# Sheet1.net
KiCad netlist of a schematic drawn in Altium Designer
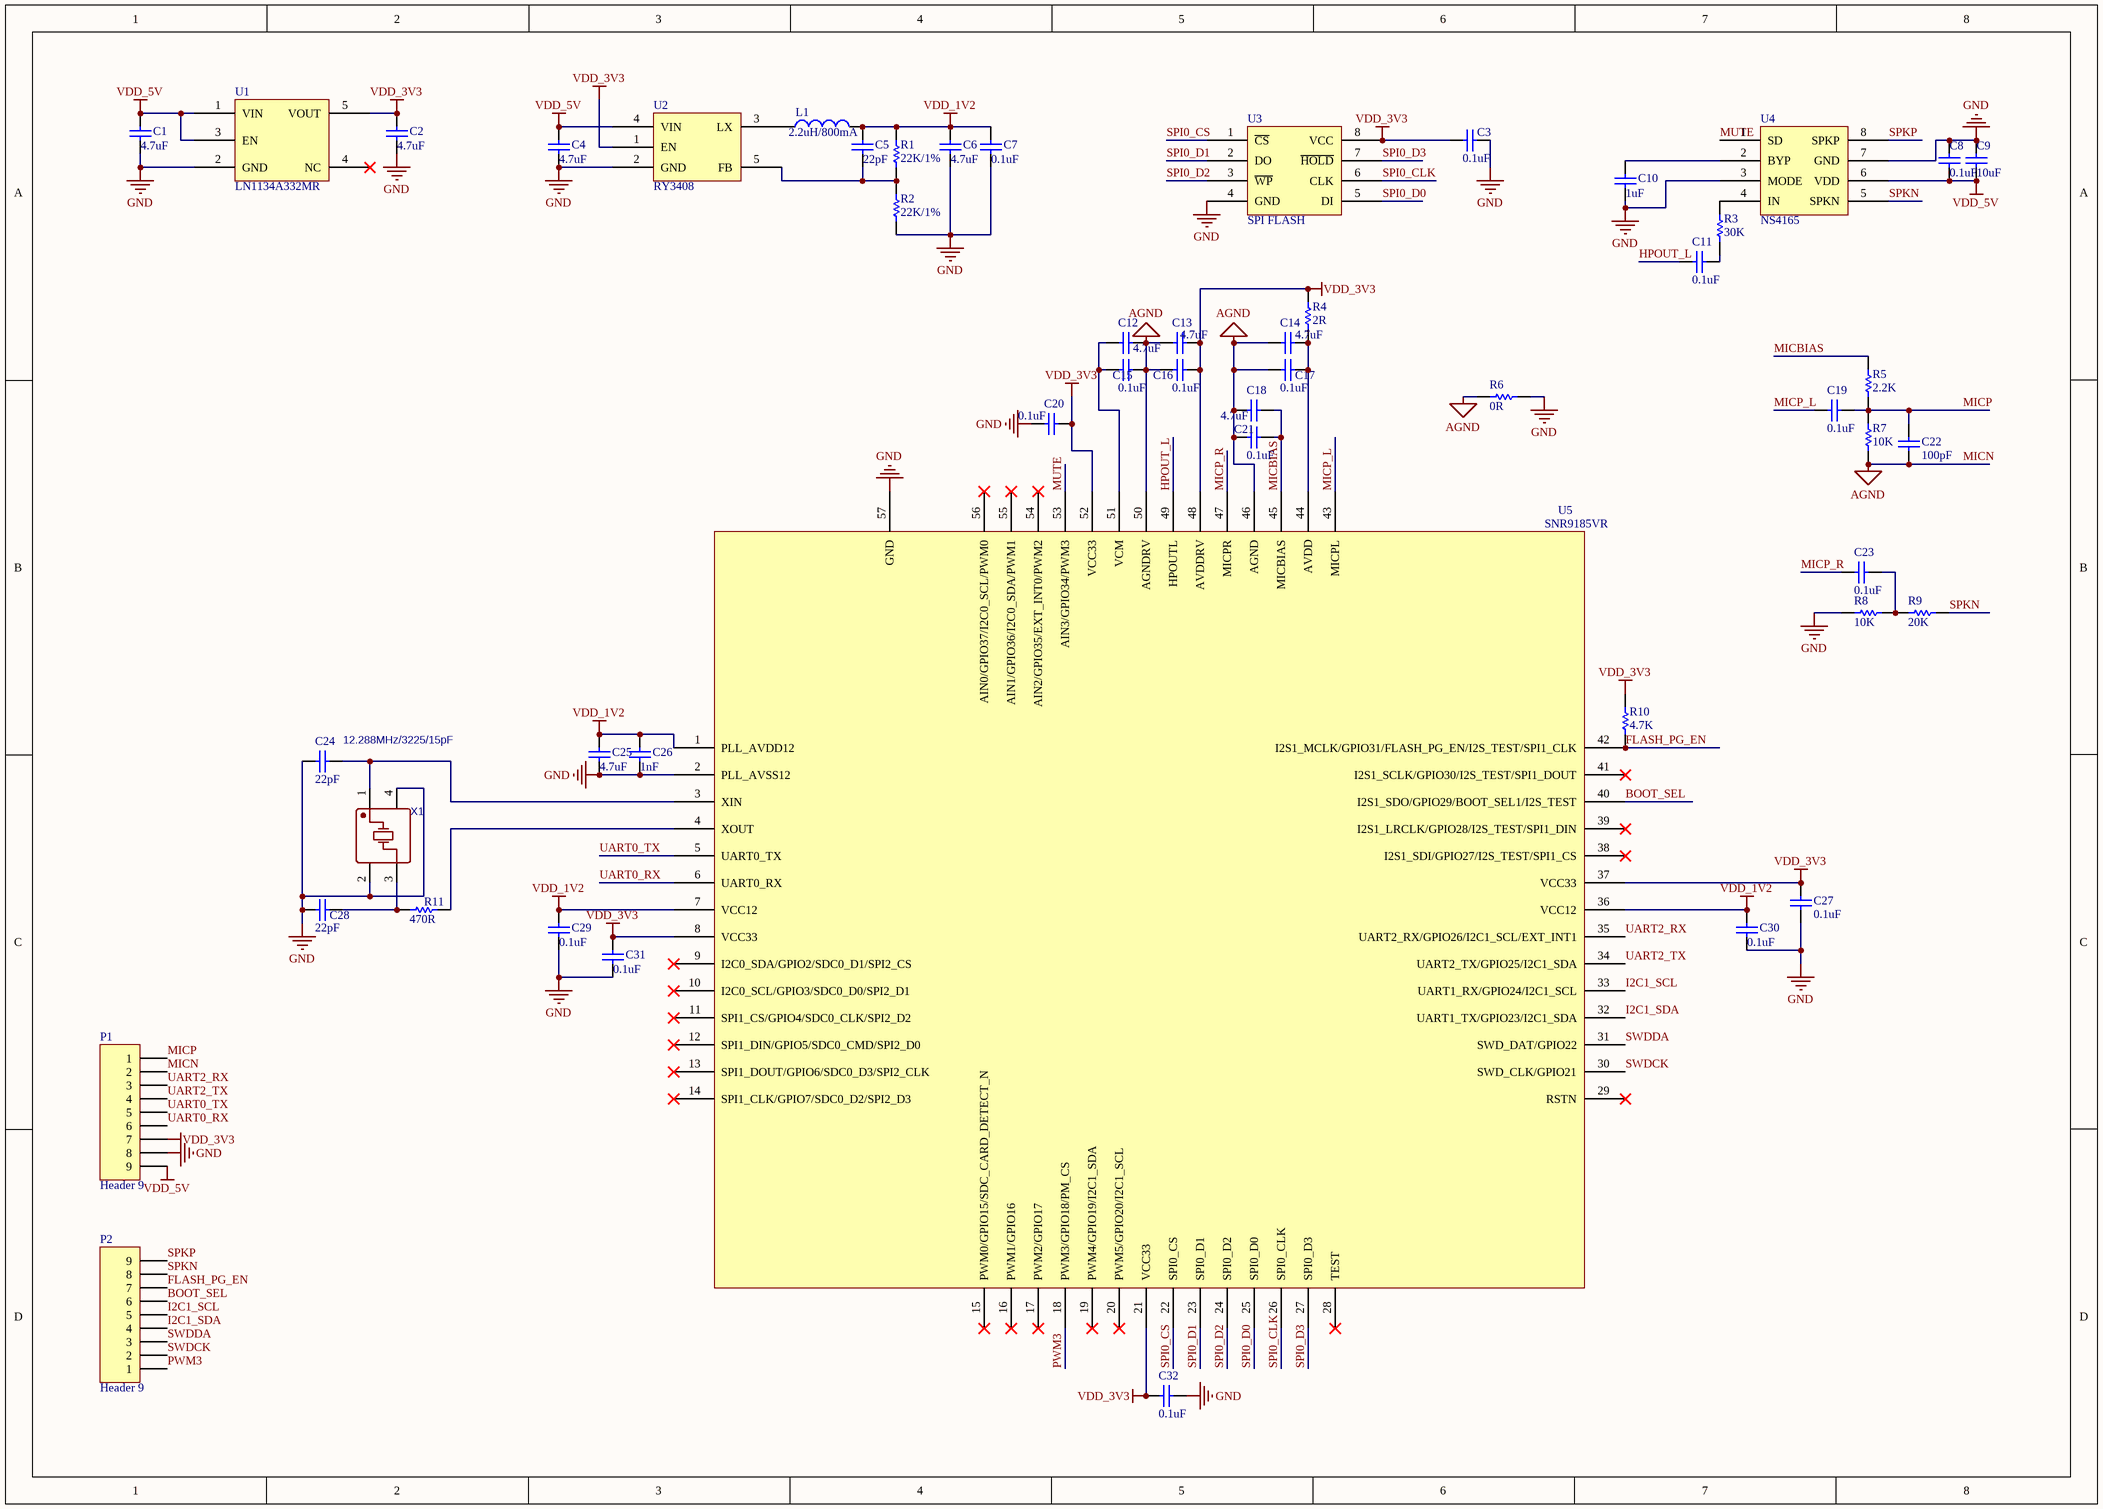
[diagram p0: Sheet1.SchDoc]

(export (version "E")
  (design (tool "Eeschema 10.0.6"))
  (components
    (comp (ref "C1")
      (value "4.7uF")
      (footprint "C0402")
      (description "Capacitor")
      (fields (field (name "Comment") "Cap") (field (name "PUBLISHER") "Altium Limited"))
      (libsource (lib "Miscellaneous Devices") (part "Cap"))
    )
    (comp (ref "C2")
      (value "4.7uF")
      (footprint "C0402")
      (description "Capacitor")
      (fields (field (name "Comment") "Cap") (field (name "PUBLISHER") "Altium Limited"))
      (libsource (lib "Miscellaneous Devices") (part "Cap"))
    )
    (comp (ref "C3")
      (value "0.1uF")
      (footprint "C0402")
      (description "Capacitor")
      (fields (field (name "Comment") "Cap") (field (name "PUBLISHER") "Altium Limited"))
      (libsource (lib "Miscellaneous Devices") (part "Cap"))
    )
    (comp (ref "C4")
      (value "4.7uF")
      (footprint "C0402")
      (description "Capacitor")
      (fields (field (name "Comment") "Cap") (field (name "PUBLISHER") "Altium Limited"))
      (libsource (lib "Miscellaneous Devices") (part "Cap"))
    )
    (comp (ref "C5")
      (value "22pF")
      (footprint "C0402")
      (description "Capacitor")
      (fields (field (name "Comment") "Cap") (field (name "PUBLISHER") "Altium Limited"))
      (libsource (lib "Miscellaneous Devices") (part "Cap"))
    )
    (comp (ref "C6")
      (value "4.7uF")
      (footprint "C0402")
      (description "Capacitor")
      (fields (field (name "Comment") "Cap") (field (name "PUBLISHER") "Altium Limited"))
      (libsource (lib "Miscellaneous Devices") (part "Cap"))
    )
    (comp (ref "C7")
      (value "0.1uF")
      (footprint "C0402")
      (description "Capacitor")
      (fields (field (name "Comment") "Cap") (field (name "PUBLISHER") "Altium Limited"))
      (libsource (lib "Miscellaneous Devices") (part "Cap"))
    )
    (comp (ref "C8")
      (value "0.1uF")
      (footprint "C0402")
      (description "Capacitor")
      (fields (field (name "Comment") "Cap") (field (name "PUBLISHER") "Altium Limited"))
      (libsource (lib "Miscellaneous Devices") (part "Cap"))
    )
    (comp (ref "C9")
      (value "10uF")
      (footprint "C0603")
      (description "Capacitor")
      (fields (field (name "Comment") "Cap") (field (name "PUBLISHER") "Altium Limited"))
      (libsource (lib "Miscellaneous Devices") (part "Cap"))
    )
    (comp (ref "C10")
      (value "1uF")
      (footprint "C0402")
      (description "Capacitor")
      (fields (field (name "Comment") "Cap") (field (name "PUBLISHER") "Altium Limited"))
      (libsource (lib "Miscellaneous Devices") (part "Cap"))
    )
    (comp (ref "C11")
      (value "0.1uF")
      (footprint "C0402")
      (description "Capacitor")
      (fields (field (name "Comment") "Cap") (field (name "PUBLISHER") "Altium Limited"))
      (libsource (lib "Miscellaneous Devices") (part "Cap"))
    )
    (comp (ref "C12")
      (value "4.7uF")
      (footprint "C0402")
      (description "Capacitor")
      (fields (field (name "Comment") "Cap") (field (name "PUBLISHER") "Altium Limited"))
      (libsource (lib "Miscellaneous Devices") (part "Cap"))
    )
    (comp (ref "C13")
      (value "4.7uF")
      (footprint "C0402")
      (description "Capacitor")
      (fields (field (name "Comment") "Cap") (field (name "PUBLISHER") "Altium Limited"))
      (libsource (lib "Miscellaneous Devices") (part "Cap"))
    )
    (comp (ref "C14")
      (value "4.7uF")
      (footprint "C0402")
      (description "Capacitor")
      (fields (field (name "Comment") "Cap") (field (name "PUBLISHER") "Altium Limited"))
      (libsource (lib "Miscellaneous Devices") (part "Cap"))
    )
    (comp (ref "C15")
      (value "0.1uF")
      (footprint "C0402")
      (description "Capacitor")
      (fields (field (name "Comment") "Cap") (field (name "PUBLISHER") "Altium Limited"))
      (libsource (lib "Miscellaneous Devices") (part "Cap"))
    )
    (comp (ref "C16")
      (value "0.1uF")
      (footprint "C0402")
      (description "Capacitor")
      (fields (field (name "Comment") "Cap") (field (name "PUBLISHER") "Altium Limited"))
      (libsource (lib "Miscellaneous Devices") (part "Cap"))
    )
    (comp (ref "C17")
      (value "0.1uF")
      (footprint "C0402")
      (description "Capacitor")
      (fields (field (name "Comment") "Cap") (field (name "PUBLISHER") "Altium Limited"))
      (libsource (lib "Miscellaneous Devices") (part "Cap"))
    )
    (comp (ref "C18")
      (value "4.7uF")
      (footprint "C0402")
      (description "Capacitor")
      (fields (field (name "Comment") "Cap") (field (name "PUBLISHER") "Altium Limited"))
      (libsource (lib "Miscellaneous Devices") (part "Cap"))
    )
    (comp (ref "C19")
      (value "0.1uF")
      (footprint "C0402")
      (description "Capacitor")
      (fields (field (name "Comment") "Cap") (field (name "PUBLISHER") "Altium Limited"))
      (libsource (lib "Miscellaneous Devices") (part "Cap"))
    )
    (comp (ref "C20")
      (value "0.1uF")
      (footprint "C0402")
      (description "Capacitor")
      (fields (field (name "Comment") "Cap") (field (name "PUBLISHER") "Altium Limited"))
      (libsource (lib "Miscellaneous Devices") (part "Cap"))
    )
    (comp (ref "C21")
      (value "0.1uF")
      (footprint "C0402")
      (description "Capacitor")
      (fields (field (name "Comment") "Cap") (field (name "PUBLISHER") "Altium Limited"))
      (libsource (lib "Miscellaneous Devices") (part "Cap"))
    )
    (comp (ref "C22")
      (value "100pF")
      (footprint "C0402")
      (description "Capacitor")
      (fields (field (name "Comment") "Cap") (field (name "PUBLISHER") "Altium Limited"))
      (libsource (lib "Miscellaneous Devices") (part "Cap"))
    )
    (comp (ref "C23")
      (value "0.1uF")
      (footprint "C0402")
      (description "Capacitor")
      (fields (field (name "Comment") "Cap") (field (name "PUBLISHER") "Altium Limited"))
      (libsource (lib "Miscellaneous Devices") (part "Cap"))
    )
    (comp (ref "C24")
      (value "22pF")
      (footprint "C0402")
      (description "Capacitor")
      (fields (field (name "Comment") "Cap") (field (name "PUBLISHER") "Altium Limited"))
      (libsource (lib "Miscellaneous Devices") (part "Cap"))
    )
    (comp (ref "C25")
      (value "4.7uF")
      (footprint "C0402")
      (description "Capacitor")
      (fields (field (name "Comment") "Cap") (field (name "PUBLISHER") "Altium Limited"))
      (libsource (lib "Miscellaneous Devices") (part "Cap"))
    )
    (comp (ref "C26")
      (value "1nF")
      (footprint "C0402")
      (description "Capacitor")
      (fields (field (name "Comment") "Cap") (field (name "PUBLISHER") "Altium Limited"))
      (libsource (lib "Miscellaneous Devices") (part "Cap"))
    )
    (comp (ref "C27")
      (value "0.1uF")
      (footprint "C0402")
      (description "Capacitor")
      (fields (field (name "Comment") "Cap") (field (name "PUBLISHER") "Altium Limited"))
      (libsource (lib "Miscellaneous Devices") (part "Cap"))
    )
    (comp (ref "C28")
      (value "22pF")
      (footprint "C0402")
      (description "Capacitor")
      (fields (field (name "Comment") "Cap") (field (name "PUBLISHER") "Altium Limited"))
      (libsource (lib "Miscellaneous Devices") (part "Cap"))
    )
    (comp (ref "C29")
      (value "0.1uF")
      (footprint "C0402")
      (description "Capacitor")
      (fields (field (name "Comment") "Cap") (field (name "PUBLISHER") "Altium Limited"))
      (libsource (lib "Miscellaneous Devices") (part "Cap"))
    )
    (comp (ref "C30")
      (value "0.1uF")
      (footprint "C0402")
      (description "Capacitor")
      (fields (field (name "Comment") "Cap") (field (name "PUBLISHER") "Altium Limited"))
      (libsource (lib "Miscellaneous Devices") (part "Cap"))
    )
    (comp (ref "C31")
      (value "0.1uF")
      (footprint "C0402")
      (description "Capacitor")
      (fields (field (name "Comment") "Cap") (field (name "PUBLISHER") "Altium Limited"))
      (libsource (lib "Miscellaneous Devices") (part "Cap"))
    )
    (comp (ref "C32")
      (value "0.1uF")
      (footprint "C0402")
      (description "Capacitor")
      (fields (field (name "Comment") "Cap") (field (name "PUBLISHER") "Altium Limited"))
      (libsource (lib "Miscellaneous Devices") (part "Cap"))
    )
    (comp (ref "L1")
      (value "2.2uH/800mA")
      (footprint "0805_L")
      (description "Inductor")
      (fields (field (name "PUBLISHER") "Altium Limited"))
      (libsource (lib "Miscellaneous Devices") (part "Inductor"))
    )
    (comp (ref "P1")
      (value "Header 9")
      (footprint "Header 1*9P 2.54mm-2")
      (description "Header, 9-Pin")
      (fields (field (name "PUBLISHER") "Altium Limited"))
      (libsource (lib "") (part "Header 9_1"))
    )
    (comp (ref "P2")
      (value "Header 9")
      (footprint "Header 1*9P 2.54mm-2")
      (description "Header, 9-Pin")
      (fields (field (name "PUBLISHER") "Altium Limited"))
      (libsource (lib "Miscellaneous Connectors") (part "Header 9"))
    )
    (comp (ref "R1")
      (value "22K/1%")
      (footprint "R0402")
      (description "Resistor")
      (fields (field (name "Comment") "Res1") (field (name "PUBLISHER") "Altium Limited"))
      (libsource (lib "Miscellaneous Devices") (part "Res1"))
    )
    (comp (ref "R2")
      (value "22K/1%")
      (footprint "R0402")
      (description "Resistor")
      (fields (field (name "Comment") "Res1") (field (name "PUBLISHER") "Altium Limited"))
      (libsource (lib "Miscellaneous Devices") (part "Res1"))
    )
    (comp (ref "R3")
      (value "30K")
      (footprint "R0402")
      (description "Resistor")
      (fields (field (name "Comment") "Res1") (field (name "PUBLISHER") "Altium Limited"))
      (libsource (lib "Miscellaneous Devices") (part "Res1"))
    )
    (comp (ref "R4")
      (value "2R")
      (footprint "R0402")
      (description "Resistor")
      (fields (field (name "Comment") "Res1") (field (name "PUBLISHER") "Altium Limited"))
      (libsource (lib "Miscellaneous Devices") (part "Res1"))
    )
    (comp (ref "R5")
      (value "2.2K")
      (footprint "R0402")
      (description "Resistor")
      (fields (field (name "Comment") "Res1") (field (name "PUBLISHER") "Altium Limited"))
      (libsource (lib "Miscellaneous Devices") (part "Res1"))
    )
    (comp (ref "R6")
      (value "0R")
      (footprint "R0402")
      (description "Resistor")
      (fields (field (name "Comment") "Res1") (field (name "PUBLISHER") "Altium Limited"))
      (libsource (lib "Miscellaneous Devices") (part "Res1"))
    )
    (comp (ref "R7")
      (value "10K")
      (footprint "R0402")
      (description "Resistor")
      (fields (field (name "Comment") "Res1") (field (name "PUBLISHER") "Altium Limited"))
      (libsource (lib "Miscellaneous Devices") (part "Res1"))
    )
    (comp (ref "R8")
      (value "10K")
      (footprint "R0402")
      (description "Resistor")
      (fields (field (name "Comment") "Res1") (field (name "PUBLISHER") "Altium Limited"))
      (libsource (lib "Miscellaneous Devices") (part "Res1"))
    )
    (comp (ref "R9")
      (value "20K")
      (footprint "R0402")
      (description "Resistor")
      (fields (field (name "Comment") "Res1") (field (name "PUBLISHER") "Altium Limited"))
      (libsource (lib "Miscellaneous Devices") (part "Res1"))
    )
    (comp (ref "R10")
      (value "4.7K")
      (footprint "R0402")
      (description "Resistor")
      (fields (field (name "Comment") "Res1") (field (name "PUBLISHER") "Altium Limited"))
      (libsource (lib "Miscellaneous Devices") (part "Res1"))
    )
    (comp (ref "R11")
      (value "470R")
      (footprint "R0402")
      (description "Resistor")
      (fields (field (name "Comment") "Res1") (field (name "PUBLISHER") "Altium Limited"))
      (libsource (lib "Miscellaneous Devices") (part "Res1"))
    )
    (comp (ref "U1")
      (value "LN1134A332MR")
      (footprint "SOT-23-5")
      (libsource (lib "SNANER—SCH库") (part "LIN1134A332MR"))
    )
    (comp (ref "U2") (value "RY3408") (footprint "SOT-23-5") (libsource (lib "SNANER—SCH库") (part "RY3408")))
    (comp (ref "U3")
      (value "SPI FLASH")
      (footprint "SOIC-8_208MIL")
      (libsource (lib "SNANER—SCH库") (part "SPI FLASH"))
    )
    (comp (ref "U4") (value "NS4165") (footprint "NS4165") (libsource (lib "SNANER—SCH库") (part "NS4165")))
    (comp (ref "U5")
      (value "SNR9185VR")
      (footprint "QFN-56_L7.0-W7.0-P0.40-BL-EP5.1")
      (libsource (lib "SNANER—SCH库") (part "SNR9185VR"))
    )
    (comp (ref "X1")
      (value "12.288MHz/3225/15pF")
      (footprint "OSC-SMD_4P-L3.2-W2.5-BL")
      (fields
        (field (name "BOM_SUPPLIER PART") "C362472")
        (field (name "BOM_MANUFACTURER PART") "SMD-3225_4P 12.288MHZ 12PF")
        (field (name "CONTRIBUTOR") "LCSC")
      )
      (libsource (lib "SNANER—SCH库") (part "12.288MHz"))
    )
  )
  (nets
    (net (code "1") (name "/BOOT_SEL") (class "Default")
      (node (ref "P2") (pin "6") (pinfunction "6_6") (pintype "passive"))
      (node (ref "U5") (pin "40") (pinfunction "I2S1_SDO/GPIO29/BOOT_SEL1/I2S_TEST_40") (pintype "passive"))
    )
    (net (code "2") (name "/FLASH_PG_EN") (class "Default")
      (node (ref "P2") (pin "7") (pinfunction "7_7") (pintype "passive"))
      (node (ref "R10") (pin "2") (pinfunction "2_2") (pintype "passive"))
      (node (ref "U5") (pin "42") (pinfunction "I2S1_MCLK/GPIO31/FLASH_PG_EN/I2S_TEST/SPI1_CLK_42") (pintype "passive"))
    )
    (net (code "3") (name "/HPOUT_L") (class "Default")
      (node (ref "C11") (pin "1") (pinfunction "1_1") (pintype "passive"))
      (node (ref "U5") (pin "49") (pinfunction "HPOUTL_49") (pintype "passive"))
    )
    (net (code "4") (name "/I2C1_SCL") (class "Default")
      (node (ref "P2") (pin "5") (pinfunction "5_5") (pintype "passive"))
      (node (ref "U5") (pin "33") (pinfunction "UART1_RX/GPIO24/I2C1_SCL_33") (pintype "passive"))
    )
    (net (code "5") (name "/I2C1_SDA") (class "Default")
      (node (ref "P2") (pin "4") (pinfunction "4_4") (pintype "passive"))
      (node (ref "U5") (pin "32") (pinfunction "UART1_TX/GPIO23/I2C1_SDA_32") (pintype "passive"))
    )
    (net (code "6") (name "/MICBIAS") (class "Default")
      (node (ref "C18") (pin "2") (pinfunction "2_2") (pintype "passive"))
      (node (ref "C21") (pin "1") (pinfunction "1_1") (pintype "passive"))
      (node (ref "R5") (pin "2") (pinfunction "2_2") (pintype "passive"))
      (node (ref "U5") (pin "45") (pinfunction "MICBIAS_45") (pintype "passive"))
    )
    (net (code "7") (name "/MICP") (class "Default")
      (node (ref "C19") (pin "1") (pinfunction "1_1") (pintype "passive"))
      (node (ref "C22") (pin "1") (pinfunction "1_1") (pintype "passive"))
      (node (ref "P1") (pin "1") (pinfunction "1_1") (pintype "passive"))
      (node (ref "R5") (pin "1") (pinfunction "1_1") (pintype "passive"))
      (node (ref "R7") (pin "2") (pinfunction "2_2") (pintype "passive"))
    )
    (net (code "8") (name "/MICP_L") (class "Default")
      (node (ref "C19") (pin "2") (pinfunction "2_2") (pintype "passive"))
      (node (ref "U5") (pin "43") (pinfunction "MICPL_43") (pintype "passive"))
    )
    (net (code "9") (name "/MICP_R") (class "Default")
      (node (ref "C23") (pin "2") (pinfunction "2_2") (pintype "passive"))
      (node (ref "U5") (pin "47") (pinfunction "MICPR_47") (pintype "passive"))
    )
    (net (code "10") (name "/MUTE") (class "Default")
      (node (ref "U4") (pin "1") (pinfunction "SD_1") (pintype "passive"))
      (node (ref "U5") (pin "53") (pinfunction "AIN3/GPIO34/PWM3_53") (pintype "passive"))
    )
    (net (code "11") (name "/PWM3") (class "Default")
      (node (ref "P2") (pin "1") (pinfunction "1_1") (pintype "passive"))
      (node (ref "U5") (pin "18") (pinfunction "PWM3/GPIO18/PM_CS_18") (pintype "passive"))
    )
    (net (code "12") (name "/SPI0_CLK") (class "Default")
      (node (ref "U3") (pin "6") (pinfunction "CLK_6") (pintype "passive"))
      (node (ref "U5") (pin "26") (pinfunction "SPI0_CLK_26") (pintype "passive"))
    )
    (net (code "13") (name "/SPI0_CS") (class "Default")
      (node (ref "U3") (pin "1") (pinfunction "~{CS}_1") (pintype "passive"))
      (node (ref "U5") (pin "22") (pinfunction "SPI0_CS_22") (pintype "passive"))
    )
    (net (code "14") (name "/SPI0_D0") (class "Default")
      (node (ref "U3") (pin "5") (pinfunction "DI_5") (pintype "passive"))
      (node (ref "U5") (pin "25") (pinfunction "SPI0_D0_25") (pintype "passive"))
    )
    (net (code "15") (name "/SPI0_D1") (class "Default")
      (node (ref "U3") (pin "2") (pinfunction "DO_2") (pintype "passive"))
      (node (ref "U5") (pin "23") (pinfunction "SPI0_D1_23") (pintype "passive"))
    )
    (net (code "16") (name "/SPI0_D2") (class "Default")
      (node (ref "U3") (pin "3") (pinfunction "~{WP}_3") (pintype "passive"))
      (node (ref "U5") (pin "24") (pinfunction "SPI0_D2_24") (pintype "passive"))
    )
    (net (code "17") (name "/SPI0_D3") (class "Default")
      (node (ref "U3") (pin "7") (pinfunction "~{HOLD}_7") (pintype "passive"))
      (node (ref "U5") (pin "27") (pinfunction "SPI0_D3_27") (pintype "passive"))
    )
    (net (code "18") (name "/SPKN") (class "Default")
      (node (ref "P2") (pin "8") (pinfunction "8_8") (pintype "passive"))
      (node (ref "R9") (pin "1") (pinfunction "1_1") (pintype "passive"))
      (node (ref "U4") (pin "5") (pinfunction "SPKN_5") (pintype "passive"))
    )
    (net (code "19") (name "/SPKP") (class "Default")
      (node (ref "P2") (pin "9") (pinfunction "9_9") (pintype "passive"))
      (node (ref "U4") (pin "8") (pinfunction "SPKP_8") (pintype "passive"))
    )
    (net (code "20") (name "/SWDCK") (class "Default")
      (node (ref "P2") (pin "2") (pinfunction "2_2") (pintype "passive"))
      (node (ref "U5") (pin "30") (pinfunction "SWD_CLK/GPIO21_30") (pintype "passive"))
    )
    (net (code "21") (name "/SWDDA") (class "Default")
      (node (ref "P2") (pin "3") (pinfunction "3_3") (pintype "passive"))
      (node (ref "U5") (pin "31") (pinfunction "SWD_DAT/GPIO22_31") (pintype "passive"))
    )
    (net (code "22") (name "/UART0_RX") (class "Default")
      (node (ref "P1") (pin "6") (pinfunction "6_6") (pintype "passive"))
      (node (ref "U5") (pin "6") (pinfunction "UART0_RX_6") (pintype "passive"))
    )
    (net (code "23") (name "/UART0_TX") (class "Default")
      (node (ref "P1") (pin "5") (pinfunction "5_5") (pintype "passive"))
      (node (ref "U5") (pin "5") (pinfunction "UART0_TX_5") (pintype "passive"))
    )
    (net (code "24") (name "/UART2_RX") (class "Default")
      (node (ref "P1") (pin "3") (pinfunction "3_3") (pintype "passive"))
      (node (ref "U5") (pin "35") (pinfunction "UART2_RX/GPIO26/I2C1_SCL/EXT_INT1_35") (pintype "passive"))
    )
    (net (code "25") (name "/UART2_TX") (class "Default")
      (node (ref "P1") (pin "4") (pinfunction "4_4") (pintype "passive"))
      (node (ref "U5") (pin "34") (pinfunction "UART2_TX/GPIO25/I2C1_SDA_34") (pintype "passive"))
    )
    (net (code "26") (name "AGND") (class "Default")
      (node (ref "C12") (pin "2") (pinfunction "2_2") (pintype "passive"))
      (node (ref "C13") (pin "1") (pinfunction "1_1") (pintype "passive"))
      (node (ref "C14") (pin "2") (pinfunction "2_2") (pintype "passive"))
      (node (ref "C15") (pin "1") (pinfunction "1_1") (pintype "passive"))
      (node (ref "C16") (pin "2") (pinfunction "2_2") (pintype "passive"))
      (node (ref "C17") (pin "1") (pinfunction "1_1") (pintype "passive"))
      (node (ref "C18") (pin "1") (pinfunction "1_1") (pintype "passive"))
      (node (ref "C21") (pin "2") (pinfunction "2_2") (pintype "passive"))
      (node (ref "C22") (pin "2") (pinfunction "2_2") (pintype "passive"))
      (node (ref "P1") (pin "2") (pinfunction "2_2") (pintype "passive"))
      (node (ref "R6") (pin "2") (pinfunction "2_2") (pintype "passive"))
      (node (ref "R7") (pin "1") (pinfunction "1_1") (pintype "passive"))
      (node (ref "U5") (pin "46") (pinfunction "AGND_46") (pintype "passive"))
      (node (ref "U5") (pin "50") (pinfunction "AGNDRV_50") (pintype "passive"))
    )
    (net (code "27") (name "GND") (class "Default")
      (node (ref "C1") (pin "1") (pinfunction "1_1") (pintype "passive"))
      (node (ref "C10") (pin "1") (pinfunction "1_1") (pintype "passive"))
      (node (ref "C2") (pin "1") (pinfunction "1_1") (pintype "passive"))
      (node (ref "C20") (pin "1") (pinfunction "1_1") (pintype "passive"))
      (node (ref "C24") (pin "2") (pinfunction "2_2") (pintype "passive"))
      (node (ref "C25") (pin "1") (pinfunction "1_1") (pintype "passive"))
      (node (ref "C26") (pin "1") (pinfunction "1_1") (pintype "passive"))
      (node (ref "C27") (pin "1") (pinfunction "1_1") (pintype "passive"))
      (node (ref "C28") (pin "2") (pinfunction "2_2") (pintype "passive"))
      (node (ref "C29") (pin "1") (pinfunction "1_1") (pintype "passive"))
      (node (ref "C3") (pin "1") (pinfunction "1_1") (pintype "passive"))
      (node (ref "C30") (pin "1") (pinfunction "1_1") (pintype "passive"))
      (node (ref "C31") (pin "1") (pinfunction "1_1") (pintype "passive"))
      (node (ref "C32") (pin "1") (pinfunction "1_1") (pintype "passive"))
      (node (ref "C4") (pin "1") (pinfunction "1_1") (pintype "passive"))
      (node (ref "C6") (pin "1") (pinfunction "1_1") (pintype "passive"))
      (node (ref "C7") (pin "1") (pinfunction "1_1") (pintype "passive"))
      (node (ref "C8") (pin "1") (pinfunction "1_1") (pintype "passive"))
      (node (ref "C9") (pin "2") (pinfunction "2_2") (pintype "passive"))
      (node (ref "P1") (pin "8") (pinfunction "8_8") (pintype "passive"))
      (node (ref "R2") (pin "1") (pinfunction "1_1") (pintype "passive"))
      (node (ref "R6") (pin "1") (pinfunction "1_1") (pintype "passive"))
      (node (ref "R8") (pin "2") (pinfunction "2_2") (pintype "passive"))
      (node (ref "U1") (pin "2") (pinfunction "GND_2") (pintype "passive"))
      (node (ref "U2") (pin "2") (pinfunction "GND_2") (pintype "passive"))
      (node (ref "U3") (pin "4") (pinfunction "GND_4") (pintype "passive"))
      (node (ref "U4") (pin "3") (pinfunction "MODE_3") (pintype "passive"))
      (node (ref "U4") (pin "7") (pinfunction "GND_7") (pintype "passive"))
      (node (ref "U5") (pin "2") (pinfunction "PLL_AVSS12_2") (pintype "passive"))
      (node (ref "U5") (pin "57") (pinfunction "GND_57") (pintype "passive"))
      (node (ref "X1") (pin "2") (pinfunction "GND_2") (pintype "passive"))
      (node (ref "X1") (pin "4") (pinfunction "GND_4") (pintype "passive"))
    )
    (net (code "28") (name "Net-(C11-Pad2)") (class "Default")
      (node (ref "C11") (pin "2") (pinfunction "2_2") (pintype "passive"))
      (node (ref "R3") (pin "2") (pinfunction "2_2") (pintype "passive"))
    )
    (net (code "29") (name "Net-(C23-Pad1)") (class "Default")
      (node (ref "C23") (pin "1") (pinfunction "1_1") (pintype "passive"))
      (node (ref "R8") (pin "1") (pinfunction "1_1") (pintype "passive"))
      (node (ref "R9") (pin "2") (pinfunction "2_2") (pintype "passive"))
    )
    (net (code "30") (name "Net-(U2-FB)") (class "Default")
      (node (ref "C5") (pin "1") (pinfunction "1_1") (pintype "passive"))
      (node (ref "R1") (pin "1") (pinfunction "1_1") (pintype "passive"))
      (node (ref "R2") (pin "2") (pinfunction "2_2") (pintype "passive"))
      (node (ref "U2") (pin "5") (pinfunction "FB_5") (pintype "passive"))
    )
    (net (code "31") (name "Net-(U2-LX)") (class "Default")
      (node (ref "L1") (pin "1") (pinfunction "1_1") (pintype "passive"))
      (node (ref "U2") (pin "3") (pinfunction "LX_3") (pintype "passive"))
    )
    (net (code "32") (name "Net-(U4-BYP)") (class "Default")
      (node (ref "C10") (pin "2") (pinfunction "2_2") (pintype "passive"))
      (node (ref "U4") (pin "2") (pinfunction "BYP_2") (pintype "passive"))
    )
    (net (code "33") (name "Net-(U4-IN)") (class "Default")
      (node (ref "R3") (pin "1") (pinfunction "1_1") (pintype "passive"))
      (node (ref "U4") (pin "4") (pinfunction "IN_4") (pintype "passive"))
    )
    (net (code "34") (name "Net-(U5-AVDD)") (class "Default")
      (node (ref "C14") (pin "1") (pinfunction "1_1") (pintype "passive"))
      (node (ref "C17") (pin "2") (pinfunction "2_2") (pintype "passive"))
      (node (ref "R4") (pin "2") (pinfunction "2_2") (pintype "passive"))
      (node (ref "U5") (pin "44") (pinfunction "AVDD_44") (pintype "passive"))
    )
    (net (code "35") (name "Net-(U5-VCM)") (class "Default")
      (node (ref "C12") (pin "1") (pinfunction "1_1") (pintype "passive"))
      (node (ref "C15") (pin "2") (pinfunction "2_2") (pintype "passive"))
      (node (ref "U5") (pin "51") (pinfunction "VCM_51") (pintype "passive"))
    )
    (net (code "36") (name "Net-(U5-XIN)") (class "Default")
      (node (ref "C24") (pin "1") (pinfunction "1_1") (pintype "passive"))
      (node (ref "U5") (pin "3") (pinfunction "XIN_3") (pintype "passive"))
      (node (ref "X1") (pin "1") (pinfunction "OE#_1") (pintype "passive"))
    )
    (net (code "37") (name "Net-(U5-XOUT)") (class "Default")
      (node (ref "R11") (pin "1") (pinfunction "1_1") (pintype "passive"))
      (node (ref "U5") (pin "4") (pinfunction "XOUT_4") (pintype "passive"))
    )
    (net (code "38") (name "Net-(X1-OUT)") (class "Default")
      (node (ref "C28") (pin "1") (pinfunction "1_1") (pintype "passive"))
      (node (ref "R11") (pin "2") (pinfunction "2_2") (pintype "passive"))
      (node (ref "X1") (pin "3") (pinfunction "OUT_3") (pintype "passive"))
    )
    (net (code "39") (name "VDD_1V2") (class "Default")
      (node (ref "C25") (pin "2") (pinfunction "2_2") (pintype "passive"))
      (node (ref "C26") (pin "2") (pinfunction "2_2") (pintype "passive"))
      (node (ref "C29") (pin "2") (pinfunction "2_2") (pintype "passive"))
      (node (ref "C30") (pin "2") (pinfunction "2_2") (pintype "passive"))
      (node (ref "C5") (pin "2") (pinfunction "2_2") (pintype "passive"))
      (node (ref "C6") (pin "2") (pinfunction "2_2") (pintype "passive"))
      (node (ref "C7") (pin "2") (pinfunction "2_2") (pintype "passive"))
      (node (ref "L1") (pin "2") (pinfunction "2_2") (pintype "passive"))
      (node (ref "R1") (pin "2") (pinfunction "2_2") (pintype "passive"))
      (node (ref "U5") (pin "1") (pinfunction "PLL_AVDD12_1") (pintype "passive"))
      (node (ref "U5") (pin "36") (pinfunction "VCC12_36") (pintype "passive"))
      (node (ref "U5") (pin "7") (pinfunction "VCC12_7") (pintype "passive"))
    )
    (net (code "40") (name "VDD_3V3") (class "Default")
      (node (ref "C13") (pin "2") (pinfunction "2_2") (pintype "passive"))
      (node (ref "C16") (pin "1") (pinfunction "1_1") (pintype "passive"))
      (node (ref "C2") (pin "2") (pinfunction "2_2") (pintype "passive"))
      (node (ref "C20") (pin "2") (pinfunction "2_2") (pintype "passive"))
      (node (ref "C27") (pin "2") (pinfunction "2_2") (pintype "passive"))
      (node (ref "C3") (pin "2") (pinfunction "2_2") (pintype "passive"))
      (node (ref "C31") (pin "2") (pinfunction "2_2") (pintype "passive"))
      (node (ref "C32") (pin "2") (pinfunction "2_2") (pintype "passive"))
      (node (ref "P1") (pin "7") (pinfunction "7_7") (pintype "passive"))
      (node (ref "R10") (pin "1") (pinfunction "1_1") (pintype "passive"))
      (node (ref "R4") (pin "1") (pinfunction "1_1") (pintype "passive"))
      (node (ref "U1") (pin "5") (pinfunction "VOUT_5") (pintype "passive"))
      (node (ref "U2") (pin "1") (pinfunction "EN_1") (pintype "passive"))
      (node (ref "U3") (pin "8") (pinfunction "VCC_8") (pintype "passive"))
      (node (ref "U5") (pin "21") (pinfunction "VCC33_21") (pintype "passive"))
      (node (ref "U5") (pin "37") (pinfunction "VCC33_37") (pintype "passive"))
      (node (ref "U5") (pin "48") (pinfunction "AVDDRV_48") (pintype "passive"))
      (node (ref "U5") (pin "52") (pinfunction "VCC33_52") (pintype "passive"))
      (node (ref "U5") (pin "8") (pinfunction "VCC33_8") (pintype "passive"))
    )
    (net (code "41") (name "VDD_5V") (class "Default")
      (node (ref "C1") (pin "2") (pinfunction "2_2") (pintype "passive"))
      (node (ref "C4") (pin "2") (pinfunction "2_2") (pintype "passive"))
      (node (ref "C8") (pin "2") (pinfunction "2_2") (pintype "passive"))
      (node (ref "C9") (pin "1") (pinfunction "1_1") (pintype "passive"))
      (node (ref "P1") (pin "9") (pinfunction "9_9") (pintype "passive"))
      (node (ref "U1") (pin "1") (pinfunction "VIN_1") (pintype "passive"))
      (node (ref "U1") (pin "3") (pinfunction "EN_3") (pintype "passive"))
      (node (ref "U2") (pin "4") (pinfunction "VIN_4") (pintype "passive"))
      (node (ref "U4") (pin "6") (pinfunction "VDD_6") (pintype "passive"))
    )
    (net (code "42") (name "unconnected-(U1-NC-Pad4)") (class "Default")
      (node (ref "U1") (pin "4") (pinfunction "NC_4") (pintype "passive+no_connect"))
    )
    (net (code "43") (name "unconnected-(U5-AIN0{slash}GPIO37{slash}I2C0_SCL{slash}PWM0-Pad56)") (class "Default")
      (node (ref "U5") (pin "56") (pinfunction "AIN0/GPIO37/I2C0_SCL/PWM0_56") (pintype "passive+no_connect"))
    )
    (net (code "44") (name "unconnected-(U5-AIN1{slash}GPIO36{slash}I2C0_SDA{slash}PWM1-Pad55)") (class "Default")
      (node (ref "U5") (pin "55") (pinfunction "AIN1/GPIO36/I2C0_SDA/PWM1_55") (pintype "passive+no_connect"))
    )
    (net (code "45") (name "unconnected-(U5-AIN2{slash}GPIO35{slash}EXT_INT0{slash}PWM2-Pad54)") (class "Default")
      (node (ref "U5") (pin "54") (pinfunction "AIN2/GPIO35/EXT_INT0/PWM2_54") (pintype "passive+no_connect"))
    )
    (net (code "46") (name "unconnected-(U5-I2C0_SCL{slash}GPIO3{slash}SDC0_D0{slash}SPI2_D1-Pad10)") (class "Default")
      (node (ref "U5") (pin "10") (pinfunction "I2C0_SCL/GPIO3/SDC0_D0/SPI2_D1_10") (pintype "passive+no_connect"))
    )
    (net (code "47") (name "unconnected-(U5-I2C0_SDA{slash}GPIO2{slash}SDC0_D1{slash}SPI2_CS-Pad9)") (class "Default")
      (node (ref "U5") (pin "9") (pinfunction "I2C0_SDA/GPIO2/SDC0_D1/SPI2_CS_9") (pintype "passive+no_connect"))
    )
    (net (code "48") (name "unconnected-(U5-I2S1_LRCLK{slash}GPIO28{slash}I2S_TEST{slash}SPI1_DIN-Pad39)") (class "Default")
      (node (ref "U5") (pin "39") (pinfunction "I2S1_LRCLK/GPIO28/I2S_TEST/SPI1_DIN_39") (pintype "passive+no_connect"))
    )
    (net (code "49") (name "unconnected-(U5-I2S1_SCLK{slash}GPIO30{slash}I2S_TEST{slash}SPI1_DOUT-Pad41)") (class "Default")
      (node (ref "U5") (pin "41") (pinfunction "I2S1_SCLK/GPIO30/I2S_TEST/SPI1_DOUT_41") (pintype "passive+no_connect"))
    )
    (net (code "50") (name "unconnected-(U5-I2S1_SDI{slash}GPIO27{slash}I2S_TEST{slash}SPI1_CS-Pad38)") (class "Default")
      (node (ref "U5") (pin "38") (pinfunction "I2S1_SDI/GPIO27/I2S_TEST/SPI1_CS_38") (pintype "passive+no_connect"))
    )
    (net (code "51") (name "unconnected-(U5-PWM0{slash}GPIO15{slash}SDC_CARD_DETECT_N-Pad15)") (class "Default")
      (node (ref "U5") (pin "15") (pinfunction "PWM0/GPIO15/SDC_CARD_DETECT_N_15") (pintype "passive+no_connect"))
    )
    (net (code "52") (name "unconnected-(U5-PWM1{slash}GPIO16-Pad16)") (class "Default")
      (node (ref "U5") (pin "16") (pinfunction "PWM1/GPIO16_16") (pintype "passive+no_connect"))
    )
    (net (code "53") (name "unconnected-(U5-PWM2{slash}GPIO17-Pad17)") (class "Default")
      (node (ref "U5") (pin "17") (pinfunction "PWM2/GPIO17_17") (pintype "passive+no_connect"))
    )
    (net (code "54") (name "unconnected-(U5-PWM4{slash}GPIO19{slash}I2C1_SDA-Pad19)") (class "Default")
      (node (ref "U5") (pin "19") (pinfunction "PWM4/GPIO19/I2C1_SDA_19") (pintype "passive+no_connect"))
    )
    (net (code "55") (name "unconnected-(U5-PWM5{slash}GPIO20{slash}I2C1_SCL-Pad20)") (class "Default")
      (node (ref "U5") (pin "20") (pinfunction "PWM5/GPIO20/I2C1_SCL_20") (pintype "passive+no_connect"))
    )
    (net (code "56") (name "unconnected-(U5-RSTN-Pad29)") (class "Default")
      (node (ref "U5") (pin "29") (pinfunction "RSTN_29") (pintype "passive+no_connect"))
    )
    (net (code "57") (name "unconnected-(U5-SPI1_CLK{slash}GPIO7{slash}SDC0_D2{slash}SPI2_D3-Pad14)") (class "Default")
      (node (ref "U5") (pin "14") (pinfunction "SPI1_CLK/GPIO7/SDC0_D2/SPI2_D3_14") (pintype "passive+no_connect"))
    )
    (net (code "58") (name "unconnected-(U5-SPI1_CS{slash}GPIO4{slash}SDC0_CLK{slash}SPI2_D2-Pad11)") (class "Default")
      (node (ref "U5") (pin "11") (pinfunction "SPI1_CS/GPIO4/SDC0_CLK/SPI2_D2_11") (pintype "passive+no_connect"))
    )
    (net (code "59") (name "unconnected-(U5-SPI1_DIN{slash}GPIO5{slash}SDC0_CMD{slash}SPI2_D0-Pad12)") (class "Default")
      (node (ref "U5") (pin "12") (pinfunction "SPI1_DIN/GPIO5/SDC0_CMD/SPI2_D0_12") (pintype "passive+no_connect"))
    )
    (net (code "60") (name "unconnected-(U5-SPI1_DOUT{slash}GPIO6{slash}SDC0_D3{slash}SPI2_CLK-Pad13)") (class "Default")
      (node (ref "U5") (pin "13") (pinfunction "SPI1_DOUT/GPIO6/SDC0_D3/SPI2_CLK_13") (pintype "passive+no_connect"))
    )
    (net (code "61") (name "unconnected-(U5-TEST-Pad28)") (class "Default")
      (node (ref "U5") (pin "28") (pinfunction "TEST_28") (pintype "passive+no_connect"))
    )
  )
)
